# midi.net
KiCad netlist of a schematic drawn in Altium Designer
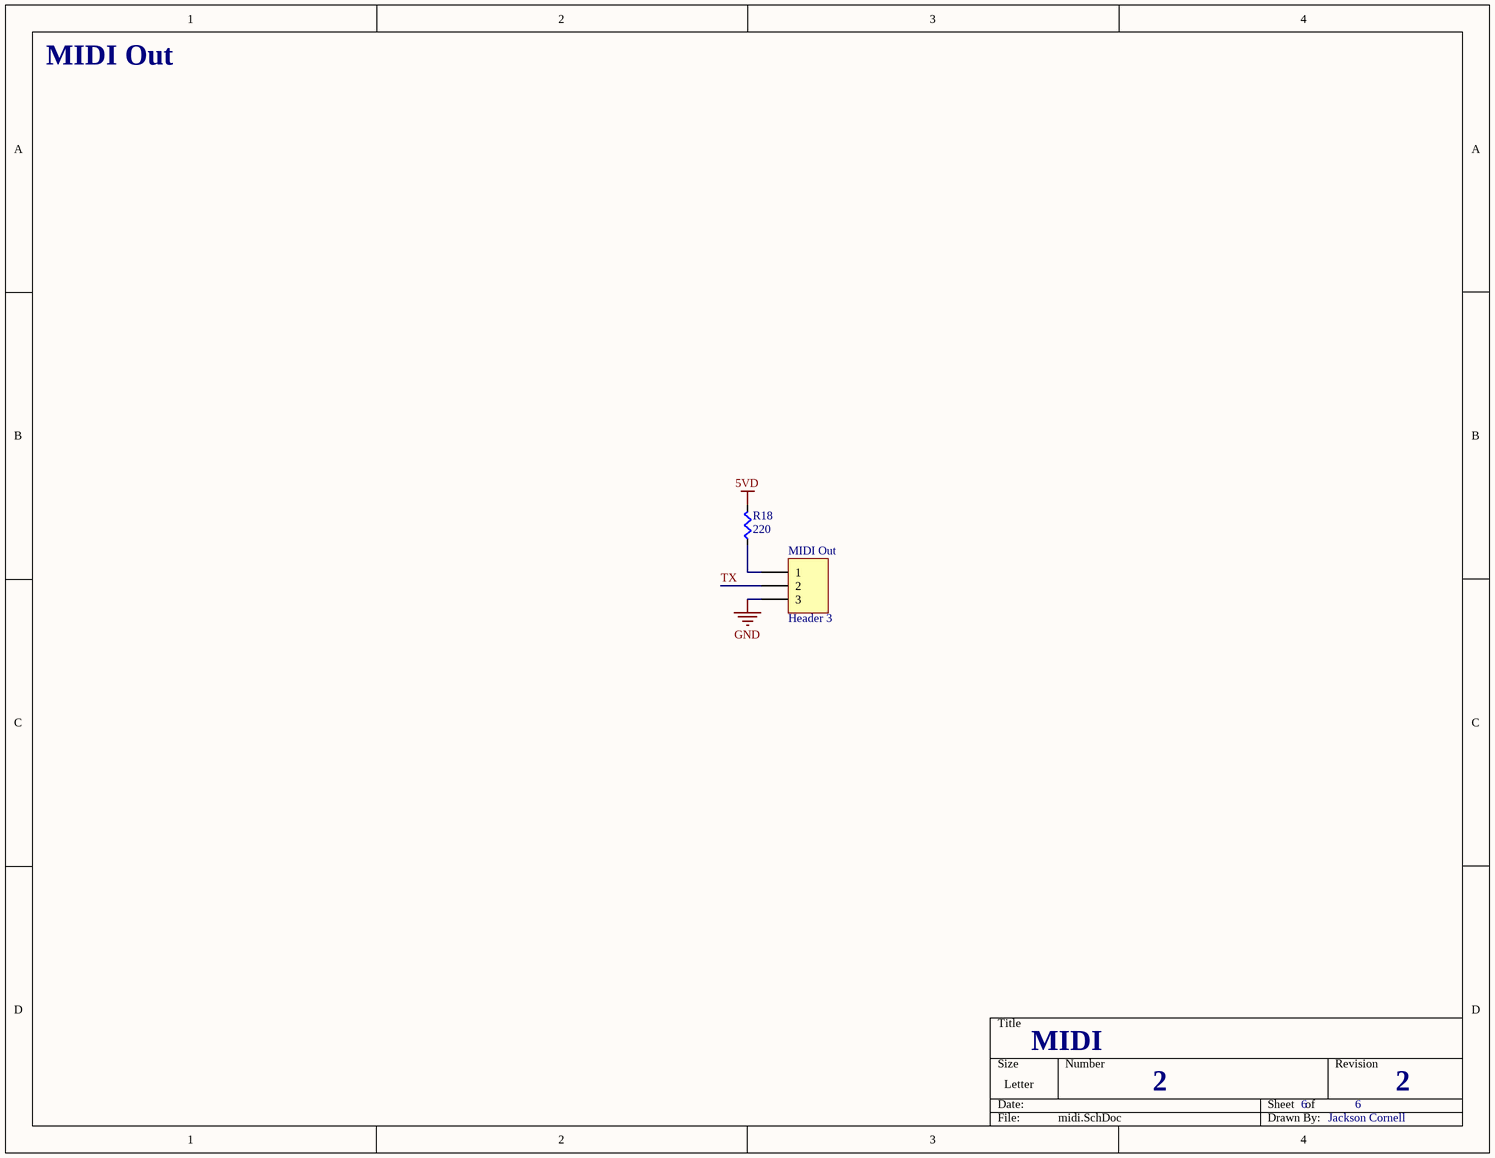
[diagram p0: midi.SchDoc]

(export (version "E")
  (design (tool "Eeschema 10.0.6"))
  (components
    (comp (ref "MIDI Out")
      (value "Header 3")
      (footprint "HDR1X3")
      (description "Header, 3-Pin")
      (fields (field (name "PUBLISHER") "Altium Limited"))
      (libsource (lib "Miscellaneous Connectors") (part "Header 3"))
    )
    (comp (ref "R18")
      (value "220")
      (footprint "RES0805")
      (fields (field (name "Comment") "Res"))
      (libsource (lib "Passives") (part "Res"))
    )
  )
  (nets
    (net (code "1") (name "/TX") (class "Default")
      (node (ref "MIDI Out") (pin "2") (pinfunction "2_2") (pintype "passive"))
    )
    (net (code "2") (name "5VD") (class "Default")
      (node (ref "R18") (pin "1") (pinfunction "A_1") (pintype "passive"))
    )
    (net (code "3") (name "GND") (class "Default")
      (node (ref "MIDI Out") (pin "3") (pinfunction "3_3") (pintype "passive"))
    )
    (net (code "4") (name "Net-(R18-B)") (class "Default")
      (node (ref "MIDI Out") (pin "1") (pinfunction "1_1") (pintype "passive"))
      (node (ref "R18") (pin "2") (pinfunction "B_2") (pintype "passive"))
    )
  )
)
